# transformer.net
KiCad netlist of a schematic drawn in Altium Designer
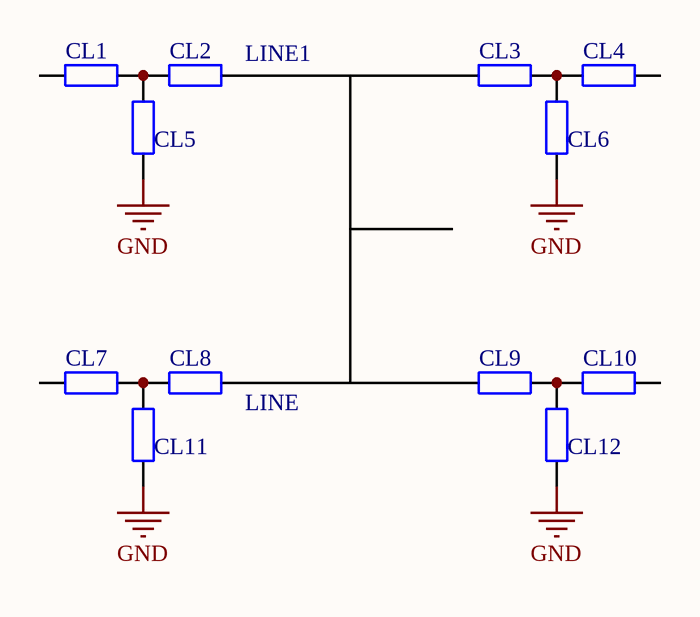
[diagram p0: transformer.SchDoc]

(export (version "E")
  (design (tool "Eeschema 10.0.6"))
  (components
    (comp (ref "CL1")
      (value "CL_component")
      (footprint "RESISTOR")
      (libsource (lib "SCH_components") (part "CL_component"))
    )
    (comp (ref "CL2")
      (value "CL_component")
      (footprint "RESISTOR")
      (libsource (lib "SCH_components") (part "CL_component"))
    )
    (comp (ref "CL3")
      (value "CL_component")
      (footprint "RESISTOR")
      (libsource (lib "SCH_components") (part "CL_component"))
    )
    (comp (ref "CL4")
      (value "CL_component")
      (footprint "RESISTOR")
      (libsource (lib "SCH_components") (part "CL_component"))
    )
    (comp (ref "CL5")
      (value "CL_component")
      (footprint "RESISTOR")
      (libsource (lib "") (part "CL_component_1"))
    )
    (comp (ref "CL6")
      (value "CL_component")
      (footprint "RESISTOR")
      (libsource (lib "") (part "CL_component_1"))
    )
    (comp (ref "CL7")
      (value "CL_component")
      (footprint "RESISTOR")
      (libsource (lib "SCH_components") (part "CL_component"))
    )
    (comp (ref "CL8")
      (value "CL_component")
      (footprint "RESISTOR")
      (libsource (lib "SCH_components") (part "CL_component"))
    )
    (comp (ref "CL9")
      (value "CL_component")
      (footprint "RESISTOR")
      (libsource (lib "SCH_components") (part "CL_component"))
    )
    (comp (ref "CL10")
      (value "CL_component")
      (footprint "RESISTOR")
      (libsource (lib "SCH_components") (part "CL_component"))
    )
    (comp (ref "CL11")
      (value "CL_component")
      (footprint "RESISTOR")
      (libsource (lib "") (part "CL_component_1"))
    )
    (comp (ref "CL12")
      (value "CL_component")
      (footprint "RESISTOR")
      (libsource (lib "") (part "CL_component_1"))
    )
    (comp (ref "LINE1") (value "LINE") (footprint "LINE") (libsource (lib "SCH_components") (part "LINE")))
  )
  (nets
    (net (code "1") (name "GND") (class "Default")
      (node (ref "CL11") (pin "1") (pinfunction "1_1") (pintype "passive"))
      (node (ref "CL12") (pin "1") (pinfunction "1_1") (pintype "passive"))
      (node (ref "CL5") (pin "1") (pinfunction "1_1") (pintype "passive"))
      (node (ref "CL6") (pin "1") (pinfunction "1_1") (pintype "passive"))
    )
    (net (code "2") (name "Net-(CL1-Pad2)") (class "Default")
      (node (ref "CL1") (pin "2") (pinfunction "2_2") (pintype "passive"))
      (node (ref "CL2") (pin "1") (pinfunction "1_1") (pintype "passive"))
      (node (ref "CL5") (pin "2") (pinfunction "2_2") (pintype "passive"))
    )
    (net (code "3") (name "Net-(CL2-Pad2)") (class "Default")
      (node (ref "CL2") (pin "2") (pinfunction "2_2") (pintype "passive"))
      (node (ref "LINE1") (pin "1") (pinfunction "1_1") (pintype "passive"))
    )
    (net (code "4") (name "Net-(CL3-Pad1)") (class "Default")
      (node (ref "CL3") (pin "1") (pinfunction "1_1") (pintype "passive"))
      (node (ref "LINE1") (pin "1") (pinfunction "1_1") (pintype "passive"))
    )
    (net (code "5") (name "Net-(CL3-Pad2)") (class "Default")
      (node (ref "CL3") (pin "2") (pinfunction "2_2") (pintype "passive"))
      (node (ref "CL4") (pin "1") (pinfunction "1_1") (pintype "passive"))
      (node (ref "CL6") (pin "2") (pinfunction "2_2") (pintype "passive"))
    )
    (net (code "6") (name "Net-(CL8-Pad2)") (class "Default")
      (node (ref "CL8") (pin "2") (pinfunction "2_2") (pintype "passive"))
      (node (ref "LINE1") (pin "1") (pinfunction "1_1") (pintype "passive"))
    )
    (net (code "7") (name "Net-(CL9-Pad1)") (class "Default")
      (node (ref "CL9") (pin "1") (pinfunction "1_1") (pintype "passive"))
      (node (ref "LINE1") (pin "1") (pinfunction "1_1") (pintype "passive"))
    )
    (net (code "8") (name "Net-(CL10-Pad1)") (class "Default")
      (node (ref "CL10") (pin "1") (pinfunction "1_1") (pintype "passive"))
      (node (ref "CL12") (pin "2") (pinfunction "2_2") (pintype "passive"))
      (node (ref "CL9") (pin "2") (pinfunction "2_2") (pintype "passive"))
    )
    (net (code "9") (name "Net-(CL11-Pad2)") (class "Default")
      (node (ref "CL11") (pin "2") (pinfunction "2_2") (pintype "passive"))
      (node (ref "CL7") (pin "2") (pinfunction "2_2") (pintype "passive"))
      (node (ref "CL8") (pin "1") (pinfunction "1_1") (pintype "passive"))
    )
    (net (code "10") (name "unconnected-(CL1-Pad1)") (class "Default")
      (node (ref "CL1") (pin "1") (pinfunction "1_1") (pintype "passive"))
    )
    (net (code "11") (name "unconnected-(CL4-Pad2)") (class "Default")
      (node (ref "CL4") (pin "2") (pinfunction "2_2") (pintype "passive"))
    )
    (net (code "12") (name "unconnected-(CL7-Pad1)") (class "Default")
      (node (ref "CL7") (pin "1") (pinfunction "1_1") (pintype "passive"))
    )
    (net (code "13") (name "unconnected-(CL10-Pad2)") (class "Default")
      (node (ref "CL10") (pin "2") (pinfunction "2_2") (pintype "passive"))
    )
    (net (code "14") (name "unconnected-(LINE1-Pad1)") (class "Default")
      (node (ref "LINE1") (pin "1") (pinfunction "1_1") (pintype "passive"))
    )
  )
)
